# custom_i2c_controller.net
KiCad netlist of a schematic drawn in EAGLE
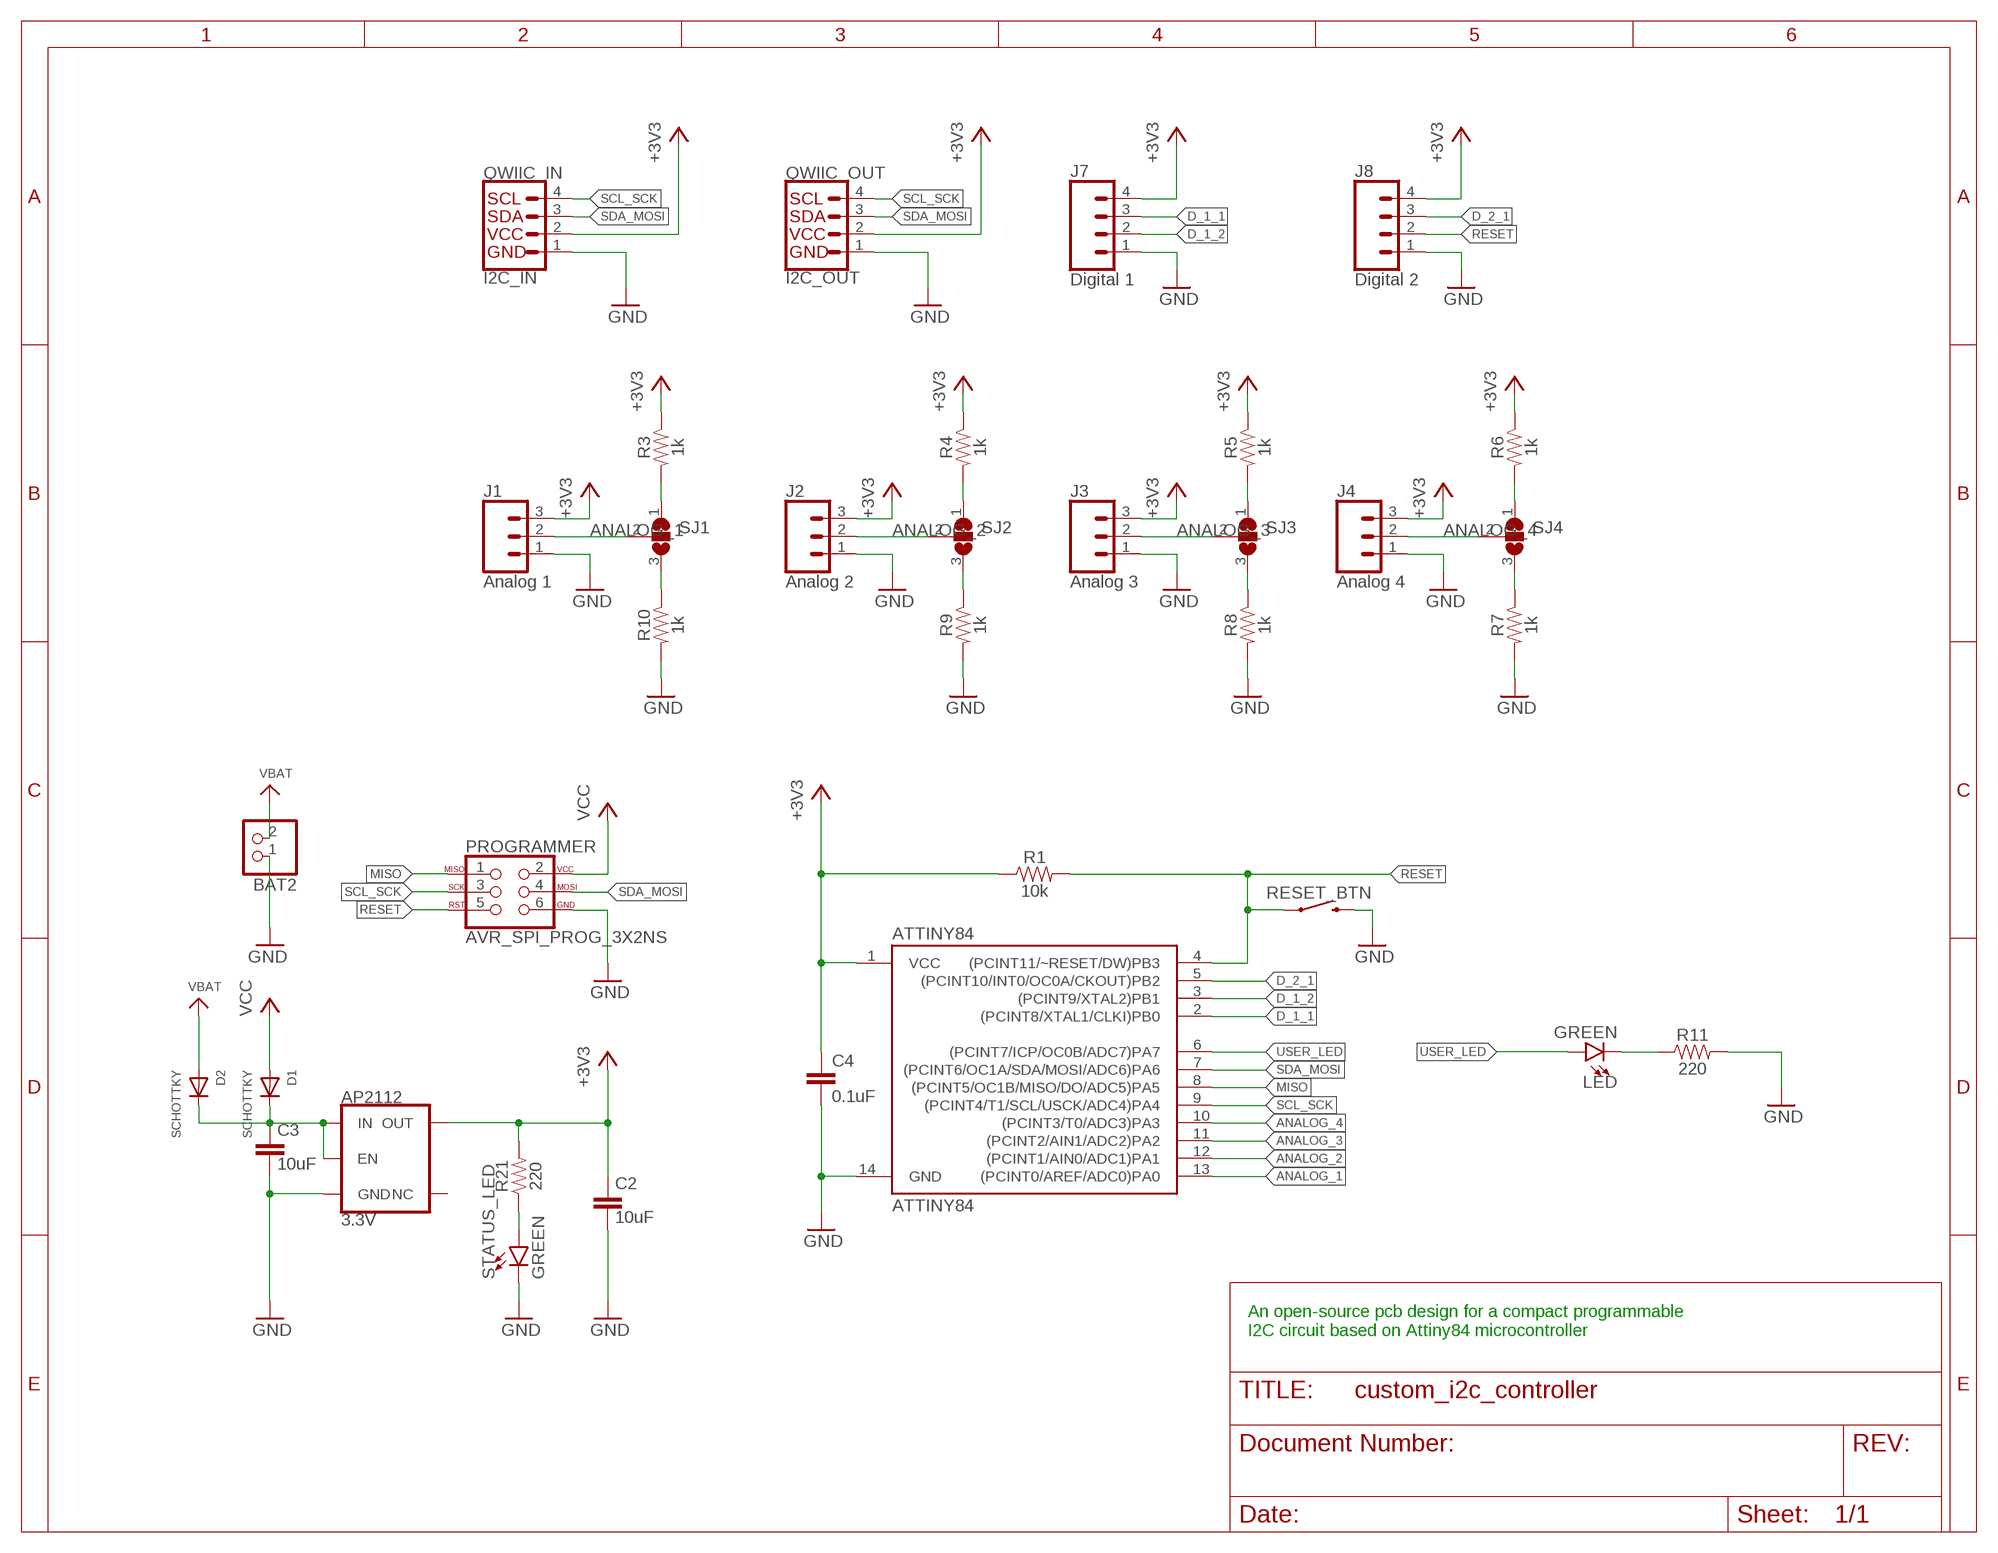
[diagram p0: schematic, sheet 1]

(export (version "E")
  (design (tool "Eeschema 10.0.6"))
  (components
    (comp (ref "AP2112")
      (value "3.3V")
      (footprint "eagle-import:SOT23-5")
      (libsource (lib "eagle-import") (part "V_REG_AP2112K-3.3V"))
    )
    (comp (ref "ATTINY84")
      (value "ATTINY84")
      (footprint "eagle-import:SO14")
      (libsource (lib "eagle-import") (part "ATTINY84"))
    )
    (comp (ref "BAT2")
      (value "CON_JST_PH_2PINSH2")
      (footprint "eagle-import:JSTSH2")
      (libsource (lib "eagle-import") (part "CON_JST_PH_2PINSH2"))
    )
    (comp (ref "C2")
      (value "10uF")
      (footprint "eagle-import:1206")
      (libsource (lib "eagle-import") (part "10UF-1206-6.3V-20%"))
    )
    (comp (ref "C3")
      (value "10uF")
      (footprint "eagle-import:1206")
      (libsource (lib "eagle-import") (part "10UF-1206-6.3V-20%"))
    )
    (comp (ref "C4")
      (value "0.1uF")
      (footprint "eagle-import:0603")
      (libsource (lib "eagle-import") (part "0.1UF-0603-25V-5%"))
    )
    (comp (ref "D1")
      (value "SCHOTTKY")
      (footprint "eagle-import:SOD-123FL")
      (libsource (lib "eagle-import") (part "DIODE_SOD-123FL"))
    )
    (comp (ref "D2")
      (value "SCHOTTKY")
      (footprint "eagle-import:SOD-123FL")
      (libsource (lib "eagle-import") (part "DIODE_SOD-123FL"))
    )
    (comp (ref "J1")
      (value "Analog 1")
      (footprint "eagle-import:1X03")
      (libsource (lib "eagle-import") (part "CONN_03"))
    )
    (comp (ref "J2")
      (value "Analog 2")
      (footprint "eagle-import:1X03")
      (libsource (lib "eagle-import") (part "CONN_03"))
    )
    (comp (ref "J3")
      (value "Analog 3")
      (footprint "eagle-import:1X03")
      (libsource (lib "eagle-import") (part "CONN_03"))
    )
    (comp (ref "J4")
      (value "Analog 4")
      (footprint "eagle-import:1X03")
      (libsource (lib "eagle-import") (part "CONN_03"))
    )
    (comp (ref "J7")
      (value "Digital 1")
      (footprint "eagle-import:1X04")
      (libsource (lib "eagle-import") (part "CONN_04"))
    )
    (comp (ref "J8")
      (value "Digital 2")
      (footprint "eagle-import:1X04")
      (libsource (lib "eagle-import") (part "CONN_04"))
    )
    (comp (ref "LED")
      (value "GREEN")
      (footprint "eagle-import:LED-0603")
      (libsource (lib "eagle-import") (part "LED-GREEN0603"))
    )
    (comp (ref "PROGRAMMER")
      (value "AVR_SPI_PROG_3X2NS")
      (footprint "eagle-import:2X3-NS")
      (libsource (lib "eagle-import") (part "AVR_SPI_PROG_3X2NS"))
    )
    (comp (ref "QWIIC_IN")
      (value "I2C_IN")
      (footprint "eagle-import:1X04_1MM_RA")
      (libsource (lib "eagle-import") (part "QWIIC_CONNECTORJS-1MM"))
    )
    (comp (ref "QWIIC_OUT")
      (value "I2C_OUT")
      (footprint "eagle-import:1X04_1MM_RA")
      (libsource (lib "eagle-import") (part "QWIIC_CONNECTORJS-1MM"))
    )
    (comp (ref "R1")
      (value "10k")
      (footprint "eagle-import:0603")
      (libsource (lib "eagle-import") (part "10KOHM-0603-1/10W-1%"))
    )
    (comp (ref "R3")
      (value "1k")
      (footprint "eagle-import:0603")
      (libsource (lib "eagle-import") (part "1KOHM-0603-1/10W-1%"))
    )
    (comp (ref "R4")
      (value "1k")
      (footprint "eagle-import:0603")
      (libsource (lib "eagle-import") (part "1KOHM-0603-1/10W-1%"))
    )
    (comp (ref "R5")
      (value "1k")
      (footprint "eagle-import:0603")
      (libsource (lib "eagle-import") (part "1KOHM-0603-1/10W-1%"))
    )
    (comp (ref "R6")
      (value "1k")
      (footprint "eagle-import:0603")
      (libsource (lib "eagle-import") (part "1KOHM-0603-1/10W-1%"))
    )
    (comp (ref "R7")
      (value "1k")
      (footprint "eagle-import:0603")
      (libsource (lib "eagle-import") (part "1KOHM-0603-1/10W-1%"))
    )
    (comp (ref "R8")
      (value "1k")
      (footprint "eagle-import:0603")
      (libsource (lib "eagle-import") (part "1KOHM-0603-1/10W-1%"))
    )
    (comp (ref "R9")
      (value "1k")
      (footprint "eagle-import:0603")
      (libsource (lib "eagle-import") (part "1KOHM-0603-1/10W-1%"))
    )
    (comp (ref "R10")
      (value "1k")
      (footprint "eagle-import:0603")
      (libsource (lib "eagle-import") (part "1KOHM-0603-1/10W-1%"))
    )
    (comp (ref "R11")
      (value "220")
      (footprint "eagle-import:0603")
      (libsource (lib "eagle-import") (part "220OHM-0603-1/10W-1%"))
    )
    (comp (ref "R21")
      (value "220")
      (footprint "eagle-import:0603")
      (libsource (lib "eagle-import") (part "220OHM-0603-1/10W-1%"))
    )
    (comp (ref "RESET_BTN")
      (value "MOMENTARY-SWITCH-SPST-SMD-6.0X3.5MM")
      (footprint "eagle-import:TACTILE_SWITCH_SMD_6.0X3.5MM")
      (libsource (lib "eagle-import") (part "MOMENTARY-SWITCH-SPST-SMD-6.0X3.5MM"))
    )
    (comp (ref "SJ1")
      (value "SJ2W")
      (footprint "eagle-import:SJ_2")
      (libsource (lib "eagle-import") (part "SJ2W"))
    )
    (comp (ref "SJ2")
      (value "SJ2W")
      (footprint "eagle-import:SJ_2")
      (libsource (lib "eagle-import") (part "SJ2W"))
    )
    (comp (ref "SJ3")
      (value "SJ2W")
      (footprint "eagle-import:SJ_2")
      (libsource (lib "eagle-import") (part "SJ2W"))
    )
    (comp (ref "SJ4")
      (value "SJ2W")
      (footprint "eagle-import:SJ_2")
      (libsource (lib "eagle-import") (part "SJ2W"))
    )
    (comp (ref "STATUS_LED")
      (value "GREEN")
      (footprint "eagle-import:LED-0603")
      (libsource (lib "eagle-import") (part "LED-GREEN0603"))
    )
  )
  (nets
    (net (code "1") (name "+3V3") (class "Default")
      (node (ref "AP2112") (pin "5") (pinfunction "OUT_5") (pintype "passive"))
      (node (ref "ATTINY84") (pin "1") (pinfunction "VCC_1") (pintype "bidirectional"))
      (node (ref "C2") (pin "1") (pinfunction "1_1") (pintype "passive"))
      (node (ref "C4") (pin "1") (pinfunction "1_1") (pintype "passive"))
      (node (ref "J1") (pin "3") (pinfunction "3_3") (pintype "passive"))
      (node (ref "J2") (pin "3") (pinfunction "3_3") (pintype "passive"))
      (node (ref "J3") (pin "3") (pinfunction "3_3") (pintype "passive"))
      (node (ref "J4") (pin "3") (pinfunction "3_3") (pintype "passive"))
      (node (ref "J7") (pin "4") (pinfunction "4_4") (pintype "passive"))
      (node (ref "J8") (pin "4") (pinfunction "4_4") (pintype "passive"))
      (node (ref "QWIIC_IN") (pin "2") (pinfunction "VCC_2") (pintype "power_in"))
      (node (ref "QWIIC_OUT") (pin "2") (pinfunction "VCC_2") (pintype "power_in"))
      (node (ref "R1") (pin "1") (pinfunction "1_1") (pintype "passive"))
      (node (ref "R21") (pin "2") (pinfunction "2_2") (pintype "passive"))
      (node (ref "R3") (pin "1") (pinfunction "1_1") (pintype "passive"))
      (node (ref "R4") (pin "1") (pinfunction "1_1") (pintype "passive"))
      (node (ref "R5") (pin "1") (pinfunction "1_1") (pintype "passive"))
      (node (ref "R6") (pin "1") (pinfunction "1_1") (pintype "passive"))
    )
    (net (code "2") (name "ANALOG_1") (class "Default")
      (node (ref "ATTINY84") (pin "13") (pinfunction "(PCINT0/AREF/ADC0)PA0_13") (pintype "bidirectional"))
      (node (ref "J1") (pin "2") (pinfunction "2_2") (pintype "passive"))
      (node (ref "SJ1") (pin "2") (pinfunction "2_2") (pintype "passive"))
    )
    (net (code "3") (name "ANALOG_2") (class "Default")
      (node (ref "ATTINY84") (pin "12") (pinfunction "(PCINT1/AIN0/ADC1)PA1_12") (pintype "bidirectional"))
      (node (ref "J2") (pin "2") (pinfunction "2_2") (pintype "passive"))
      (node (ref "SJ2") (pin "2") (pinfunction "2_2") (pintype "passive"))
    )
    (net (code "4") (name "ANALOG_3") (class "Default")
      (node (ref "ATTINY84") (pin "11") (pinfunction "(PCINT2/AIN1/ADC2)PA2_11") (pintype "bidirectional"))
      (node (ref "J3") (pin "2") (pinfunction "2_2") (pintype "passive"))
      (node (ref "SJ3") (pin "2") (pinfunction "2_2") (pintype "passive"))
    )
    (net (code "5") (name "ANALOG_4") (class "Default")
      (node (ref "ATTINY84") (pin "10") (pinfunction "(PCINT3/T0/ADC3)PA3_10") (pintype "bidirectional"))
      (node (ref "J4") (pin "2") (pinfunction "2_2") (pintype "passive"))
      (node (ref "SJ4") (pin "2") (pinfunction "2_2") (pintype "passive"))
    )
    (net (code "6") (name "D_1_1") (class "Default")
      (node (ref "ATTINY84") (pin "2") (pinfunction "(PCINT8/XTAL1/CLKI)PB0_2") (pintype "bidirectional"))
      (node (ref "J7") (pin "3") (pinfunction "3_3") (pintype "passive"))
    )
    (net (code "7") (name "D_1_2") (class "Default")
      (node (ref "ATTINY84") (pin "3") (pinfunction "(PCINT9/XTAL2)PB1_3") (pintype "bidirectional"))
      (node (ref "J7") (pin "2") (pinfunction "2_2") (pintype "passive"))
    )
    (net (code "8") (name "D_2_1") (class "Default")
      (node (ref "ATTINY84") (pin "5") (pinfunction "(PCINT10/INT0/OC0A/CKOUT)PB2_5") (pintype "bidirectional"))
      (node (ref "J8") (pin "3") (pinfunction "3_3") (pintype "passive"))
    )
    (net (code "9") (name "GND") (class "Default")
      (node (ref "AP2112") (pin "2") (pinfunction "GND_2") (pintype "input"))
      (node (ref "ATTINY84") (pin "14") (pinfunction "GND_14") (pintype "bidirectional"))
      (node (ref "BAT2") (pin "1") (pinfunction "1_1") (pintype "passive"))
      (node (ref "C2") (pin "2") (pinfunction "2_2") (pintype "passive"))
      (node (ref "C3") (pin "2") (pinfunction "2_2") (pintype "passive"))
      (node (ref "C4") (pin "2") (pinfunction "2_2") (pintype "passive"))
      (node (ref "J1") (pin "1") (pinfunction "1_1") (pintype "passive"))
      (node (ref "J2") (pin "1") (pinfunction "1_1") (pintype "passive"))
      (node (ref "J3") (pin "1") (pinfunction "1_1") (pintype "passive"))
      (node (ref "J4") (pin "1") (pinfunction "1_1") (pintype "passive"))
      (node (ref "J7") (pin "1") (pinfunction "1_1") (pintype "passive"))
      (node (ref "J8") (pin "1") (pinfunction "1_1") (pintype "passive"))
      (node (ref "PROGRAMMER") (pin "6") (pinfunction "6_6") (pintype "passive"))
      (node (ref "QWIIC_IN") (pin "1") (pinfunction "GND_1") (pintype "power_in"))
      (node (ref "QWIIC_OUT") (pin "1") (pinfunction "GND_1") (pintype "power_in"))
      (node (ref "R10") (pin "2") (pinfunction "2_2") (pintype "passive"))
      (node (ref "R11") (pin "2") (pinfunction "2_2") (pintype "passive"))
      (node (ref "R7") (pin "2") (pinfunction "2_2") (pintype "passive"))
      (node (ref "R8") (pin "2") (pinfunction "2_2") (pintype "passive"))
      (node (ref "R9") (pin "2") (pinfunction "2_2") (pintype "passive"))
      (node (ref "RESET_BTN") (pin "2") (pinfunction "2_2") (pintype "passive"))
      (node (ref "STATUS_LED") (pin "C") (pinfunction "C_C") (pintype "passive"))
    )
    (net (code "10") (name "MISO") (class "Default")
      (node (ref "ATTINY84") (pin "8") (pinfunction "(PCINT5/OC1B/MISO/DO/ADC5)PA5_8") (pintype "bidirectional"))
      (node (ref "PROGRAMMER") (pin "1") (pinfunction "1_1") (pintype "passive"))
    )
    (net (code "11") (name "Net-(AP2112-EN)") (class "Default")
      (node (ref "AP2112") (pin "1") (pinfunction "IN_1") (pintype "input"))
      (node (ref "AP2112") (pin "3") (pinfunction "EN_3") (pintype "input"))
      (node (ref "C3") (pin "1") (pinfunction "1_1") (pintype "passive"))
      (node (ref "D1") (pin "C") (pinfunction "C_C") (pintype "passive"))
      (node (ref "D2") (pin "C") (pinfunction "C_C") (pintype "passive"))
    )
    (net (code "12") (name "Net-(LED-PadC)") (class "Default")
      (node (ref "LED") (pin "C") (pinfunction "C_C") (pintype "passive"))
      (node (ref "R11") (pin "1") (pinfunction "1_1") (pintype "passive"))
    )
    (net (code "13") (name "Net-(R3-Pad2)") (class "Default")
      (node (ref "R3") (pin "2") (pinfunction "2_2") (pintype "passive"))
      (node (ref "SJ1") (pin "1") (pinfunction "1_1") (pintype "passive"))
    )
    (net (code "14") (name "Net-(R4-Pad2)") (class "Default")
      (node (ref "R4") (pin "2") (pinfunction "2_2") (pintype "passive"))
      (node (ref "SJ2") (pin "1") (pinfunction "1_1") (pintype "passive"))
    )
    (net (code "15") (name "Net-(R5-Pad2)") (class "Default")
      (node (ref "R5") (pin "2") (pinfunction "2_2") (pintype "passive"))
      (node (ref "SJ3") (pin "1") (pinfunction "1_1") (pintype "passive"))
    )
    (net (code "16") (name "Net-(R6-Pad2)") (class "Default")
      (node (ref "R6") (pin "2") (pinfunction "2_2") (pintype "passive"))
      (node (ref "SJ4") (pin "1") (pinfunction "1_1") (pintype "passive"))
    )
    (net (code "17") (name "Net-(R7-Pad1)") (class "Default")
      (node (ref "R7") (pin "1") (pinfunction "1_1") (pintype "passive"))
      (node (ref "SJ4") (pin "3") (pinfunction "3_3") (pintype "passive"))
    )
    (net (code "18") (name "Net-(R8-Pad1)") (class "Default")
      (node (ref "R8") (pin "1") (pinfunction "1_1") (pintype "passive"))
      (node (ref "SJ3") (pin "3") (pinfunction "3_3") (pintype "passive"))
    )
    (net (code "19") (name "Net-(R9-Pad1)") (class "Default")
      (node (ref "R9") (pin "1") (pinfunction "1_1") (pintype "passive"))
      (node (ref "SJ2") (pin "3") (pinfunction "3_3") (pintype "passive"))
    )
    (net (code "20") (name "Net-(R10-Pad1)") (class "Default")
      (node (ref "R10") (pin "1") (pinfunction "1_1") (pintype "passive"))
      (node (ref "SJ1") (pin "3") (pinfunction "3_3") (pintype "passive"))
    )
    (net (code "21") (name "Net-(R21-Pad1)") (class "Default")
      (node (ref "R21") (pin "1") (pinfunction "1_1") (pintype "passive"))
      (node (ref "STATUS_LED") (pin "A") (pinfunction "A_A") (pintype "passive"))
    )
    (net (code "22") (name "RESET") (class "Default")
      (node (ref "ATTINY84") (pin "4") (pinfunction "(PCINT11/~{RESET/DW})PB3_4") (pintype "bidirectional"))
      (node (ref "J8") (pin "2") (pinfunction "2_2") (pintype "passive"))
      (node (ref "PROGRAMMER") (pin "5") (pinfunction "5_5") (pintype "passive"))
      (node (ref "R1") (pin "2") (pinfunction "2_2") (pintype "passive"))
      (node (ref "RESET_BTN") (pin "1") (pinfunction "1_1") (pintype "passive"))
    )
    (net (code "23") (name "SCL_SCK") (class "Default")
      (node (ref "ATTINY84") (pin "9") (pinfunction "(PCINT4/T1/SCL/USCK/ADC4)PA4_9") (pintype "bidirectional"))
      (node (ref "PROGRAMMER") (pin "3") (pinfunction "3_3") (pintype "passive"))
      (node (ref "QWIIC_IN") (pin "4") (pinfunction "SCL_4") (pintype "passive"))
      (node (ref "QWIIC_OUT") (pin "4") (pinfunction "SCL_4") (pintype "passive"))
    )
    (net (code "24") (name "SDA_MOSI") (class "Default")
      (node (ref "ATTINY84") (pin "7") (pinfunction "(PCINT6/OC1A/SDA/MOSI/ADC6)PA6_7") (pintype "bidirectional"))
      (node (ref "PROGRAMMER") (pin "4") (pinfunction "4_4") (pintype "passive"))
      (node (ref "QWIIC_IN") (pin "3") (pinfunction "SDA_3") (pintype "passive"))
      (node (ref "QWIIC_OUT") (pin "3") (pinfunction "SDA_3") (pintype "passive"))
    )
    (net (code "25") (name "USER_LED") (class "Default")
      (node (ref "ATTINY84") (pin "6") (pinfunction "(PCINT7/ICP/OC0B/ADC7)PA7_6") (pintype "bidirectional"))
      (node (ref "LED") (pin "A") (pinfunction "A_A") (pintype "passive"))
    )
    (net (code "26") (name "VBAT") (class "Default")
      (node (ref "BAT2") (pin "2") (pinfunction "2_2") (pintype "passive"))
      (node (ref "D2") (pin "A") (pinfunction "A_A") (pintype "passive"))
    )
    (net (code "27") (name "VCC") (class "Default")
      (node (ref "D1") (pin "A") (pinfunction "A_A") (pintype "passive"))
      (node (ref "PROGRAMMER") (pin "2") (pinfunction "2_2") (pintype "passive"))
    )
    (net (code "28") (name "unconnected-(AP2112-NC-Pad4)") (class "Default")
      (node (ref "AP2112") (pin "4") (pinfunction "NC_4") (pintype "no_connect"))
    )
  )
)
